# ECUEXT1_23.net
KiCad netlist of a schematic drawn in Altium Designer
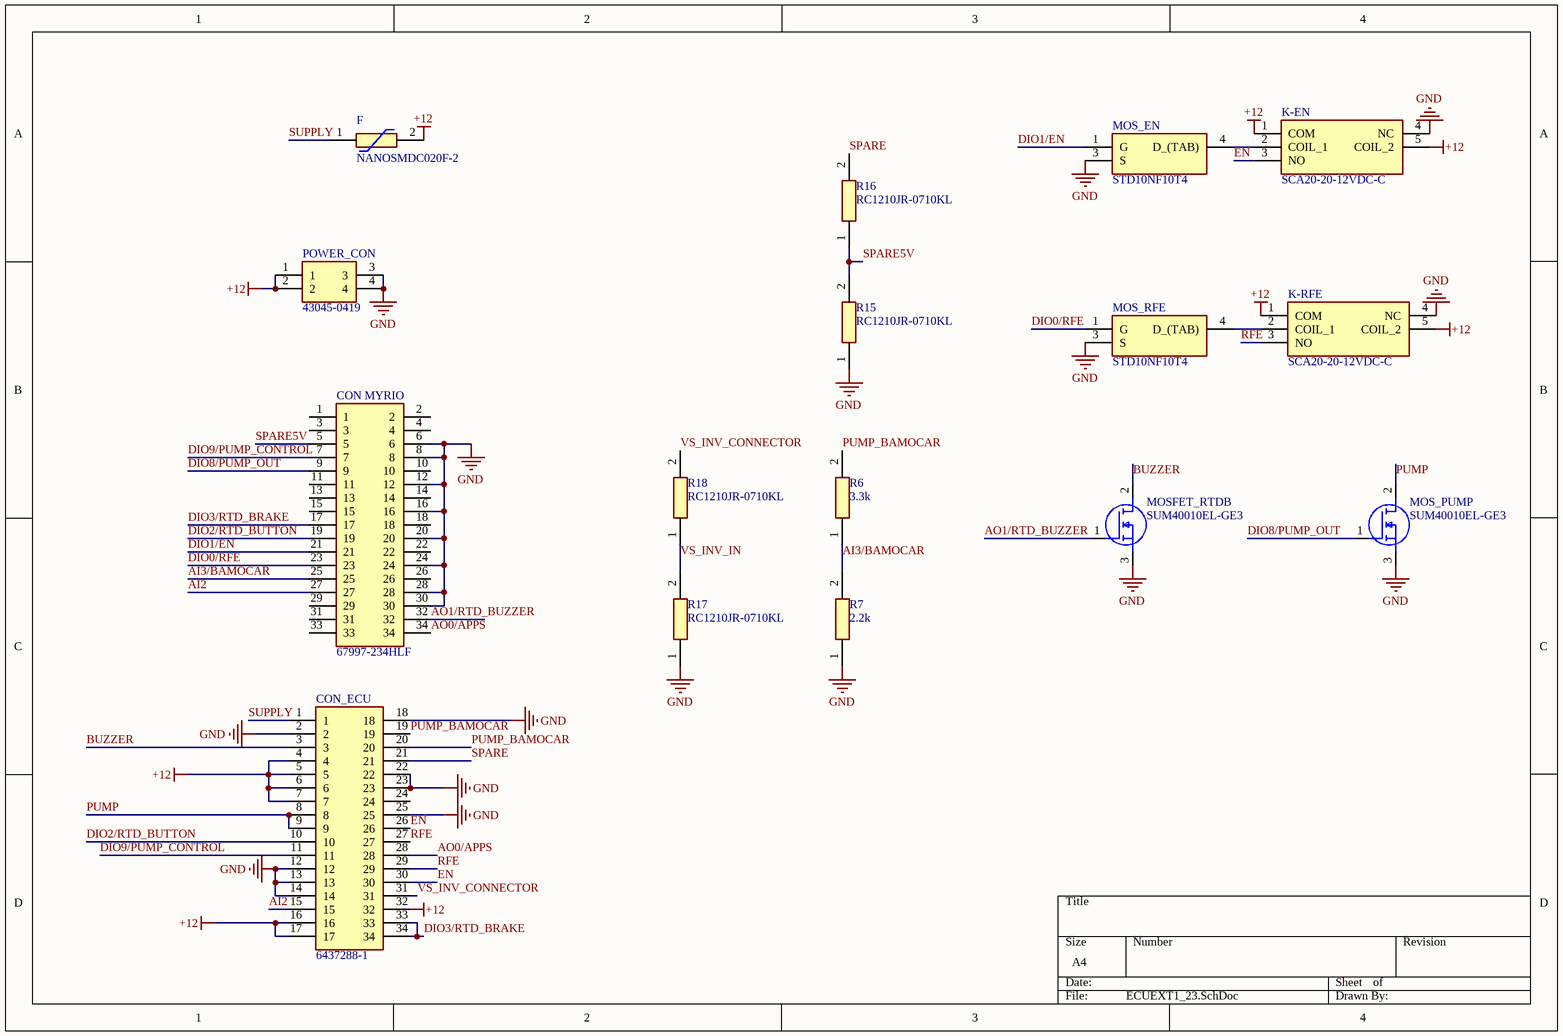
[diagram p0: ECUEXT1_23.SchDoc]

(export (version "E")
  (design (tool "Eeschema 10.0.6"))
  (components
    (comp (ref "CON MYRIO")
      (value "67997-234HLF")
      (footprint "SamacSys:HDRV34W67P254_2X17_4318X483X858P")
      (description "Connector")
      (fields (field (name "MOUSER PART NUMBER") "649-67997-234HLF"))
      (libsource (lib "*") (part "67997-234HLF"))
    )
    (comp (ref "CON_ECU")
      (value "6437288-1")
      (footprint "SamacSys:6437288-1")
      (description "Connector")
      (fields (field (name "MOUSER PART NUMBER") "571-6437288-1"))
      (libsource (lib "SamacSys") (part "6437288-1"))
    )
    (comp (ref "F")
      (value "NANOSMDC020F-2")
      (footprint "SamacSys:NANOSMDC016F2")
      (description "Resettable Fuse")
      (fields (field (name "MOUSER PART NUMBER") "650-NANOSMDC020F-2"))
      (libsource (lib "*") (part "NANOSMDC020F-2"))
    )
    (comp (ref "K-EN")
      (value "SCA20-20-12VDC-C")
      (footprint "SamacSys:SCA202012VDCC")
      (description "Relay or Contactor")
      (libsource (lib "SamacSys") (part "SCA20-20-12VDC-C"))
    )
    (comp (ref "K-RFE")
      (value "SCA20-20-12VDC-C")
      (footprint "SamacSys:SCA202012VDCC")
      (description "Relay or Contactor")
      (libsource (lib "SamacSys") (part "SCA20-20-12VDC-C"))
    )
    (comp (ref "MOSFET_RTDB")
      (value "SUM40010EL-GE3")
      (footprint "SamacSys:SUM40010ELGE3")
      (description "MOSFET (N-Channel)")
      (fields (field (name "MOUSER PART NUMBER") "78-SUM40010EL-GE3"))
      (libsource (lib "SamacSys") (part "SUM40010EL-GE3"))
    )
    (comp (ref "MOS_EN")
      (value "STD10NF10T4")
      (footprint "SamacSys:TO228P972X240-3N")
      (description "Integrated Circuit")
      (fields (field (name "MOUSER PART NUMBER") "511-STD10NF10"))
      (libsource (lib "SamacSys") (part "STD10NF10T4"))
    )
    (comp (ref "MOS_PUMP")
      (value "SUM40010EL-GE3")
      (footprint "SamacSys:SUM40010ELGE3")
      (description "MOSFET (N-Channel)")
      (fields (field (name "MOUSER PART NUMBER") "78-SUM40010EL-GE3"))
      (libsource (lib "SamacSys") (part "SUM40010EL-GE3"))
    )
    (comp (ref "MOS_RFE")
      (value "STD10NF10T4")
      (footprint "SamacSys:TO228P972X240-3N")
      (description "Integrated Circuit")
      (fields (field (name "MOUSER PART NUMBER") "511-STD10NF10"))
      (libsource (lib "SamacSys") (part "STD10NF10T4"))
    )
    (comp (ref "POWER_CON")
      (value "43045-0419")
      (footprint "SamacSys:43045-04YY_181920")
      (description "Connector")
      (fields (field (name "MOUSER PART NUMBER") "538-43045-0419"))
      (libsource (lib "SamacSys") (part "43045-0419"))
    )
    (comp (ref "R6")
      (value "3.3k")
      (footprint "SamacSys:RESC3126X60N")
      (description "Resistor")
      (fields
        (field (name "MANUFACTURER_PART_NUMBER") "RC1210JR-0710KL")
        (field (name "MOUSER PART NUMBER") "603-RC1210JR-0710KL")
      )
      (libsource (lib "*") (part "RC1210JR-0710KL"))
    )
    (comp (ref "R7")
      (value "2.2k")
      (footprint "SamacSys:RESC3126X60N")
      (description "Resistor")
      (fields
        (field (name "MANUFACTURER_PART_NUMBER") "RC1210JR-0710KL")
        (field (name "MOUSER PART NUMBER") "603-RC1210JR-0710KL")
      )
      (libsource (lib "*") (part "RC1210JR-0710KL"))
    )
    (comp (ref "R15")
      (value "RC1210JR-0710KL")
      (footprint "SamacSys:RESC3126X60N")
      (description "Resistor")
      (fields (field (name "MOUSER PART NUMBER") "603-RC1210JR-0710KL"))
      (libsource (lib "SamacSys") (part "RC1210JR-0710KL"))
    )
    (comp (ref "R16")
      (value "RC1210JR-0710KL")
      (footprint "SamacSys:RESC3126X60N")
      (description "Resistor")
      (fields (field (name "MOUSER PART NUMBER") "603-RC1210JR-0710KL"))
      (libsource (lib "SamacSys") (part "RC1210JR-0710KL"))
    )
    (comp (ref "R17")
      (value "RC1210JR-0710KL")
      (footprint "SamacSys:RESC3126X60N")
      (description "Resistor")
      (fields (field (name "MOUSER PART NUMBER") "603-RC1210JR-0710KL"))
      (libsource (lib "SamacSys") (part "RC1210JR-0710KL"))
    )
    (comp (ref "R18")
      (value "RC1210JR-0710KL")
      (footprint "SamacSys:RESC3126X60N")
      (description "Resistor")
      (fields (field (name "MOUSER PART NUMBER") "603-RC1210JR-0710KL"))
      (libsource (lib "SamacSys") (part "RC1210JR-0710KL"))
    )
  )
  (nets
    (net (code "1") (name "+12") (class "Default")
      (node (ref "CON_ECU") (pin "16") (pinfunction "16_16") (pintype "passive"))
      (node (ref "CON_ECU") (pin "17") (pinfunction "17_17") (pintype "passive"))
      (node (ref "CON_ECU") (pin "32") (pinfunction "32_32") (pintype "passive"))
      (node (ref "CON_ECU") (pin "4") (pinfunction "4_4") (pintype "passive"))
      (node (ref "CON_ECU") (pin "5") (pinfunction "5_5") (pintype "passive"))
      (node (ref "CON_ECU") (pin "6") (pinfunction "6_6") (pintype "passive"))
      (node (ref "CON_ECU") (pin "7") (pinfunction "7_7") (pintype "passive"))
      (node (ref "F") (pin "2") (pinfunction "2_2") (pintype "passive"))
      (node (ref "K-EN") (pin "1") (pinfunction "COM_1") (pintype "passive"))
      (node (ref "K-EN") (pin "5") (pinfunction "COIL_2_5") (pintype "passive"))
      (node (ref "K-RFE") (pin "1") (pinfunction "COM_1") (pintype "passive"))
      (node (ref "K-RFE") (pin "5") (pinfunction "COIL_2_5") (pintype "passive"))
      (node (ref "POWER_CON") (pin "1") (pinfunction "1_1") (pintype "passive"))
      (node (ref "POWER_CON") (pin "2") (pinfunction "2_2") (pintype "passive"))
    )
    (net (code "2") (name "/AI2") (class "Default")
      (node (ref "CON MYRIO") (pin "27") (pinfunction "27_27") (pintype "passive"))
      (node (ref "CON_ECU") (pin "15") (pinfunction "15_15") (pintype "passive"))
    )
    (net (code "3") (name "/AI3{slash}BAMOCAR") (class "Default")
      (node (ref "CON MYRIO") (pin "25") (pinfunction "25_25") (pintype "passive"))
      (node (ref "R6") (pin "1") (pinfunction "1_1") (pintype "passive"))
      (node (ref "R7") (pin "2") (pinfunction "2_2") (pintype "passive"))
    )
    (net (code "4") (name "/AO0{slash}APPS") (class "Default")
      (node (ref "CON MYRIO") (pin "34") (pinfunction "34_34") (pintype "passive"))
      (node (ref "CON_ECU") (pin "28") (pinfunction "28_28") (pintype "passive"))
    )
    (net (code "5") (name "/AO1{slash}RTD_BUZZER") (class "Default")
      (node (ref "CON MYRIO") (pin "32") (pinfunction "32_32") (pintype "passive"))
      (node (ref "MOSFET_RTDB") (pin "1") (pinfunction "G_1") (pintype "passive"))
    )
    (net (code "6") (name "/BUZZER") (class "Default")
      (node (ref "CON_ECU") (pin "3") (pinfunction "3_3") (pintype "passive"))
      (node (ref "MOSFET_RTDB") (pin "2") (pinfunction "D_2") (pintype "passive"))
    )
    (net (code "7") (name "/DIO0{slash}RFE") (class "Default")
      (node (ref "CON MYRIO") (pin "23") (pinfunction "23_23") (pintype "passive"))
      (node (ref "MOS_RFE") (pin "1") (pinfunction "G_1") (pintype "passive"))
    )
    (net (code "8") (name "/DIO1{slash}EN") (class "Default")
      (node (ref "CON MYRIO") (pin "21") (pinfunction "21_21") (pintype "passive"))
      (node (ref "MOS_EN") (pin "1") (pinfunction "G_1") (pintype "passive"))
    )
    (net (code "9") (name "/DIO2{slash}RTD_BUTTON") (class "Default")
      (node (ref "CON MYRIO") (pin "19") (pinfunction "19_19") (pintype "passive"))
      (node (ref "CON_ECU") (pin "10") (pinfunction "10_10") (pintype "passive"))
    )
    (net (code "10") (name "/DIO3{slash}RTD_BRAKE") (class "Default")
      (node (ref "CON MYRIO") (pin "17") (pinfunction "17_17") (pintype "passive"))
      (node (ref "CON_ECU") (pin "33") (pinfunction "33_33") (pintype "passive"))
      (node (ref "CON_ECU") (pin "34") (pinfunction "34_34") (pintype "passive"))
    )
    (net (code "11") (name "/DIO8{slash}PUMP_OUT") (class "Default")
      (node (ref "CON MYRIO") (pin "9") (pinfunction "9_9") (pintype "passive"))
      (node (ref "MOS_PUMP") (pin "1") (pinfunction "G_1") (pintype "passive"))
    )
    (net (code "12") (name "/DIO9{slash}PUMP_CONTROL") (class "Default")
      (node (ref "CON MYRIO") (pin "7") (pinfunction "7_7") (pintype "passive"))
      (node (ref "CON_ECU") (pin "11") (pinfunction "11_11") (pintype "passive"))
    )
    (net (code "13") (name "/EN") (class "Default")
      (node (ref "CON_ECU") (pin "26") (pinfunction "26_26") (pintype "passive"))
      (node (ref "CON_ECU") (pin "30") (pinfunction "30_30") (pintype "passive"))
      (node (ref "K-EN") (pin "3") (pinfunction "NO_3") (pintype "passive"))
    )
    (net (code "14") (name "/PUMP") (class "Default")
      (node (ref "CON_ECU") (pin "8") (pinfunction "8_8") (pintype "passive"))
      (node (ref "CON_ECU") (pin "9") (pinfunction "9_9") (pintype "passive"))
      (node (ref "MOS_PUMP") (pin "2") (pinfunction "D_2") (pintype "passive"))
    )
    (net (code "15") (name "/PUMP_BAMOCAR") (class "Default")
      (node (ref "CON_ECU") (pin "19") (pinfunction "19_19") (pintype "passive"))
      (node (ref "CON_ECU") (pin "20") (pinfunction "20_20") (pintype "passive"))
      (node (ref "R6") (pin "2") (pinfunction "2_2") (pintype "passive"))
    )
    (net (code "16") (name "/RFE") (class "Default")
      (node (ref "CON_ECU") (pin "27") (pinfunction "27_27") (pintype "passive"))
      (node (ref "CON_ECU") (pin "29") (pinfunction "29_29") (pintype "passive"))
      (node (ref "K-RFE") (pin "3") (pinfunction "NO_3") (pintype "passive"))
    )
    (net (code "17") (name "/SPARE") (class "Default")
      (node (ref "CON_ECU") (pin "21") (pinfunction "21_21") (pintype "passive"))
      (node (ref "R16") (pin "2") (pinfunction "2_2") (pintype "passive"))
    )
    (net (code "18") (name "/SPARE5V") (class "Default")
      (node (ref "CON MYRIO") (pin "5") (pinfunction "5_5") (pintype "passive"))
      (node (ref "R15") (pin "2") (pinfunction "2_2") (pintype "passive"))
      (node (ref "R16") (pin "1") (pinfunction "1_1") (pintype "passive"))
    )
    (net (code "19") (name "/SUPPLY") (class "Default")
      (node (ref "CON_ECU") (pin "1") (pinfunction "1_1") (pintype "passive"))
      (node (ref "F") (pin "1") (pinfunction "1_1") (pintype "passive"))
    )
    (net (code "20") (name "/VS_INV_CONNECTOR") (class "Default")
      (node (ref "CON_ECU") (pin "31") (pinfunction "31_31") (pintype "passive"))
      (node (ref "R18") (pin "2") (pinfunction "2_2") (pintype "passive"))
    )
    (net (code "21") (name "/VS_INV_IN") (class "Default")
      (node (ref "R17") (pin "2") (pinfunction "2_2") (pintype "passive"))
      (node (ref "R18") (pin "1") (pinfunction "1_1") (pintype "passive"))
    )
    (net (code "22") (name "GND") (class "Default")
      (node (ref "CON MYRIO") (pin "12") (pinfunction "12_12") (pintype "passive"))
      (node (ref "CON MYRIO") (pin "16") (pinfunction "16_16") (pintype "passive"))
      (node (ref "CON MYRIO") (pin "20") (pinfunction "20_20") (pintype "passive"))
      (node (ref "CON MYRIO") (pin "24") (pinfunction "24_24") (pintype "passive"))
      (node (ref "CON MYRIO") (pin "28") (pinfunction "28_28") (pintype "passive"))
      (node (ref "CON MYRIO") (pin "30") (pinfunction "30_30") (pintype "passive"))
      (node (ref "CON MYRIO") (pin "6") (pinfunction "6_6") (pintype "passive"))
      (node (ref "CON MYRIO") (pin "8") (pinfunction "8_8") (pintype "passive"))
      (node (ref "CON_ECU") (pin "12") (pinfunction "12_12") (pintype "passive"))
      (node (ref "CON_ECU") (pin "13") (pinfunction "13_13") (pintype "passive"))
      (node (ref "CON_ECU") (pin "14") (pinfunction "14_14") (pintype "passive"))
      (node (ref "CON_ECU") (pin "18") (pinfunction "18_18") (pintype "passive"))
      (node (ref "CON_ECU") (pin "2") (pinfunction "2_2") (pintype "passive"))
      (node (ref "CON_ECU") (pin "22") (pinfunction "22_22") (pintype "passive"))
      (node (ref "CON_ECU") (pin "23") (pinfunction "23_23") (pintype "passive"))
      (node (ref "CON_ECU") (pin "25") (pinfunction "25_25") (pintype "passive"))
      (node (ref "K-EN") (pin "4") (pinfunction "NC_4") (pintype "passive"))
      (node (ref "K-RFE") (pin "4") (pinfunction "NC_4") (pintype "passive"))
      (node (ref "MOSFET_RTDB") (pin "3") (pinfunction "S_3") (pintype "passive"))
      (node (ref "MOS_EN") (pin "3") (pinfunction "S_3") (pintype "passive"))
      (node (ref "MOS_PUMP") (pin "3") (pinfunction "S_3") (pintype "passive"))
      (node (ref "MOS_RFE") (pin "3") (pinfunction "S_3") (pintype "passive"))
      (node (ref "POWER_CON") (pin "3") (pinfunction "3_3") (pintype "passive"))
      (node (ref "POWER_CON") (pin "4") (pinfunction "4_4") (pintype "passive"))
      (node (ref "R15") (pin "1") (pinfunction "1_1") (pintype "passive"))
      (node (ref "R17") (pin "1") (pinfunction "1_1") (pintype "passive"))
      (node (ref "R7") (pin "1") (pinfunction "1_1") (pintype "passive"))
    )
    (net (code "23") (name "Net-(K-EN-COIL_1)") (class "Default")
      (node (ref "K-EN") (pin "2") (pinfunction "COIL_1_2") (pintype "passive"))
      (node (ref "MOS_EN") (pin "4") (pinfunction "D_(TAB)_4") (pintype "passive"))
    )
    (net (code "24") (name "Net-(K-RFE-COIL_1)") (class "Default")
      (node (ref "K-RFE") (pin "2") (pinfunction "COIL_1_2") (pintype "passive"))
      (node (ref "MOS_RFE") (pin "4") (pinfunction "D_(TAB)_4") (pintype "passive"))
    )
    (net (code "25") (name "unconnected-(CON MYRIO-Pad1)") (class "Default")
      (node (ref "CON MYRIO") (pin "1") (pinfunction "1_1") (pintype "passive"))
    )
    (net (code "26") (name "unconnected-(CON MYRIO-Pad2)") (class "Default")
      (node (ref "CON MYRIO") (pin "2") (pinfunction "2_2") (pintype "passive"))
    )
    (net (code "27") (name "unconnected-(CON MYRIO-Pad3)") (class "Default")
      (node (ref "CON MYRIO") (pin "3") (pinfunction "3_3") (pintype "passive"))
    )
    (net (code "28") (name "unconnected-(CON MYRIO-Pad4)") (class "Default")
      (node (ref "CON MYRIO") (pin "4") (pinfunction "4_4") (pintype "passive"))
    )
    (net (code "29") (name "unconnected-(CON MYRIO-Pad10)") (class "Default")
      (node (ref "CON MYRIO") (pin "10") (pinfunction "10_10") (pintype "passive"))
    )
    (net (code "30") (name "unconnected-(CON MYRIO-Pad11)") (class "Default")
      (node (ref "CON MYRIO") (pin "11") (pinfunction "11_11") (pintype "passive"))
    )
    (net (code "31") (name "unconnected-(CON MYRIO-Pad13)") (class "Default")
      (node (ref "CON MYRIO") (pin "13") (pinfunction "13_13") (pintype "passive"))
    )
    (net (code "32") (name "unconnected-(CON MYRIO-Pad14)") (class "Default")
      (node (ref "CON MYRIO") (pin "14") (pinfunction "14_14") (pintype "passive"))
    )
    (net (code "33") (name "unconnected-(CON MYRIO-Pad15)") (class "Default")
      (node (ref "CON MYRIO") (pin "15") (pinfunction "15_15") (pintype "passive"))
    )
    (net (code "34") (name "unconnected-(CON MYRIO-Pad18)") (class "Default")
      (node (ref "CON MYRIO") (pin "18") (pinfunction "18_18") (pintype "passive"))
    )
    (net (code "35") (name "unconnected-(CON MYRIO-Pad22)") (class "Default")
      (node (ref "CON MYRIO") (pin "22") (pinfunction "22_22") (pintype "passive"))
    )
    (net (code "36") (name "unconnected-(CON MYRIO-Pad26)") (class "Default")
      (node (ref "CON MYRIO") (pin "26") (pinfunction "26_26") (pintype "passive"))
    )
    (net (code "37") (name "unconnected-(CON MYRIO-Pad29)") (class "Default")
      (node (ref "CON MYRIO") (pin "29") (pinfunction "29_29") (pintype "passive"))
    )
    (net (code "38") (name "unconnected-(CON MYRIO-Pad31)") (class "Default")
      (node (ref "CON MYRIO") (pin "31") (pinfunction "31_31") (pintype "passive"))
    )
    (net (code "39") (name "unconnected-(CON MYRIO-Pad33)") (class "Default")
      (node (ref "CON MYRIO") (pin "33") (pinfunction "33_33") (pintype "passive"))
    )
    (net (code "40") (name "unconnected-(CON_ECU-Pad24)") (class "Default")
      (node (ref "CON_ECU") (pin "24") (pinfunction "24_24") (pintype "passive"))
    )
  )
)
